# 26_Clocks_2.net
KiCad netlist of a schematic drawn in Altium Designer
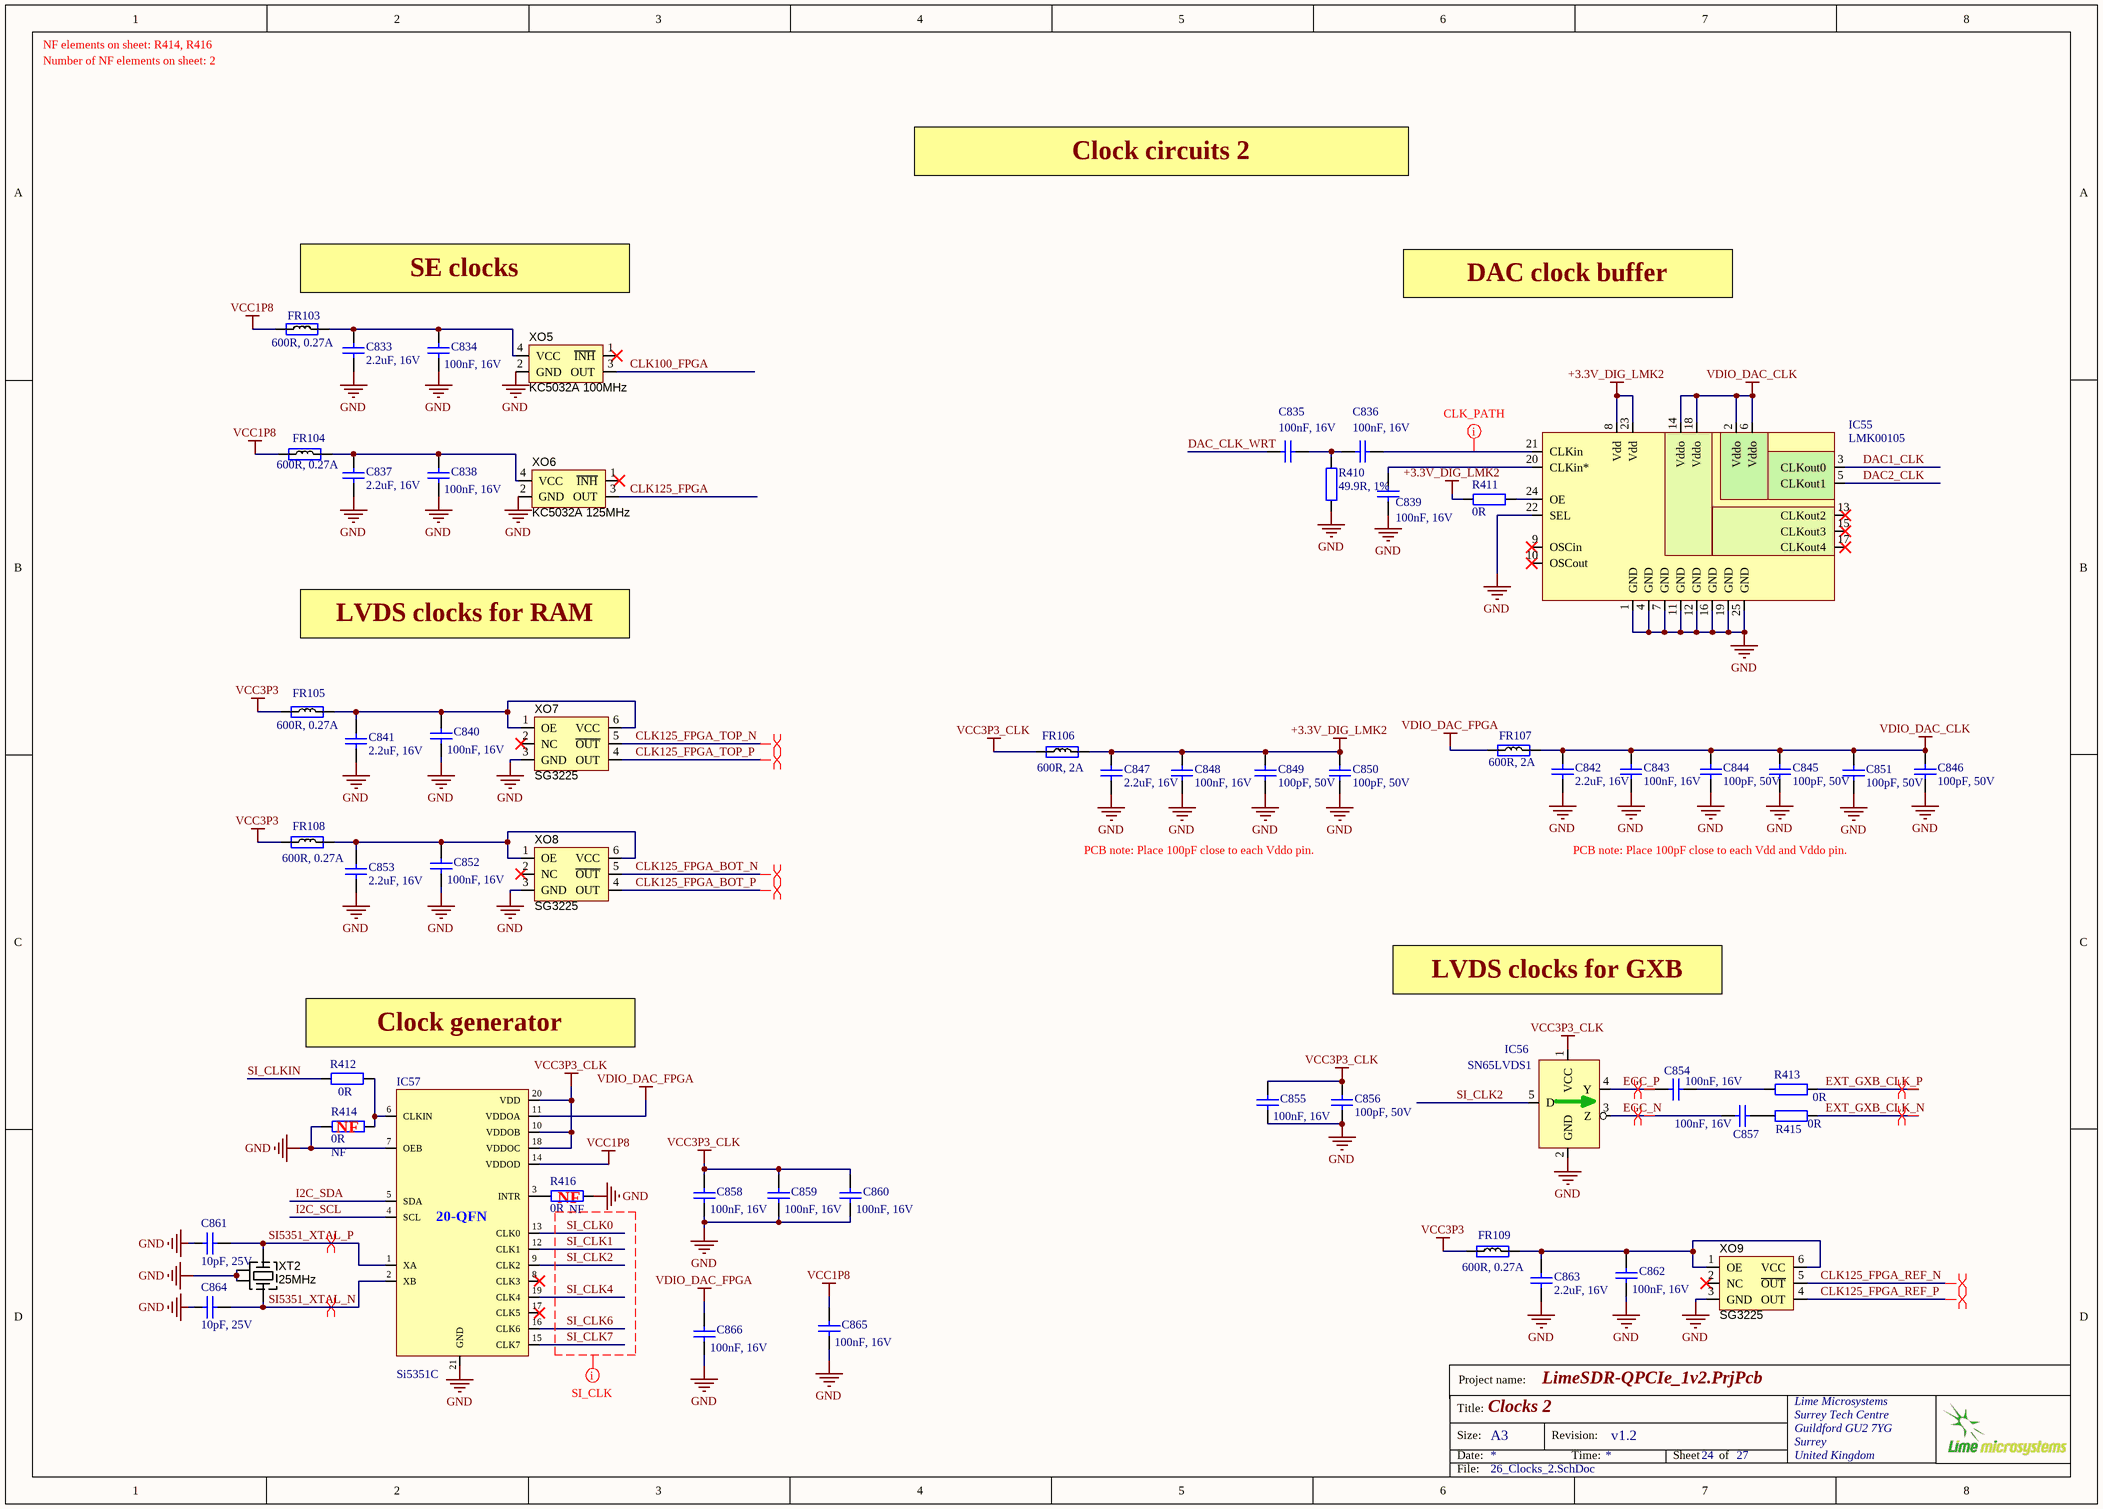
[diagram p0: 26_Clocks_2.SchDoc]

(export (version "E")
  (design (tool "Eeschema 10.0.6"))
  (components
    (comp (ref "C833")
      (value "2.2uF, 16V")
      (footprint "CAP0402")
      (description "CAP CER 2.2UF 16V 10% X5R 0402")
      (fields (field (name "MANUFACTURER") "TDK Corporation") (field (name "TOLERANCE") "±20%"))
      (libsource (lib "LimeMicroAltiumLib_schLib") (part "Cap_0402"))
    )
    (comp (ref "C834")
      (value "100nF, 16V")
      (footprint "CAP0402")
      (fields
        (field (name "TOLERANCE") "10 %")
        (field (name "MANUFACTURER") "Murata Electronics")
        (field (name "MANUFACTURER PART NUMBER") "GRM155R71C104KA88D")
      )
      (libsource (lib "LimeFPGAboard_schLib") (part "Cap_0603"))
    )
    (comp (ref "C835")
      (value "100nF, 16V")
      (footprint "CAP0402")
      (fields
        (field (name "MANUFACTURER") "Murata Electronics")
        (field (name "TOLERANCE") "10 %")
        (field (name "MANUFACTURER PART NUMBER") "GRM155R71C104KA88D")
      )
      (libsource (lib "LimeMicroAltiumLib_schLib") (part "Cap_0402"))
    )
    (comp (ref "C836")
      (value "100nF, 16V")
      (footprint "CAP0402")
      (fields
        (field (name "MANUFACTURER") "Murata Electronics")
        (field (name "TOLERANCE") "10 %")
        (field (name "MANUFACTURER PART NUMBER") "GRM155R71C104KA88D")
      )
      (libsource (lib "LimeMicroAltiumLib_schLib") (part "Cap_0402"))
    )
    (comp (ref "C837")
      (value "2.2uF, 16V")
      (footprint "CAP0402")
      (description "CAP CER 2.2UF 16V 10% X5R 0402")
      (fields (field (name "MANUFACTURER") "TDK Corporation") (field (name "TOLERANCE") "±20%"))
      (libsource (lib "LimeMicroAltiumLib_schLib") (part "Cap_0402"))
    )
    (comp (ref "C838")
      (value "100nF, 16V")
      (footprint "CAP0402")
      (fields
        (field (name "TOLERANCE") "10 %")
        (field (name "MANUFACTURER") "Murata Electronics")
        (field (name "MANUFACTURER PART NUMBER") "GRM155R71C104KA88D")
      )
      (libsource (lib "LimeFPGAboard_schLib") (part "Cap_0603"))
    )
    (comp (ref "C839")
      (value "100nF, 16V")
      (footprint "CAP0402")
      (fields
        (field (name "MANUFACTURER") "Murata Electronics")
        (field (name "TOLERANCE") "10 %")
        (field (name "MANUFACTURER PART NUMBER") "GRM155R71C104KA88D")
      )
      (libsource (lib "LimeMicroAltiumLib_schLib") (part "Cap_0402"))
    )
    (comp (ref "C840")
      (value "100nF, 16V")
      (footprint "CAP0402")
      (fields
        (field (name "TOLERANCE") "10 %")
        (field (name "MANUFACTURER") "Murata Electronics")
        (field (name "MANUFACTURER PART NUMBER") "GRM155R71C104KA88D")
      )
      (libsource (lib "LimeFPGAboard_schLib") (part "Cap_0603"))
    )
    (comp (ref "C841")
      (value "2.2uF, 16V")
      (footprint "CAP0402")
      (description "CAP CER 2.2UF 16V 10% X5R 0402")
      (fields (field (name "MANUFACTURER") "TDK Corporation") (field (name "TOLERANCE") "±20%"))
      (libsource (lib "LimeMicroAltiumLib_schLib") (part "Cap_0402"))
    )
    (comp (ref "C842")
      (value "2.2uF, 16V")
      (footprint "CAP0402")
      (description "CAP CER 2.2UF 16V 10% X5R 0402")
      (fields (field (name "MANUFACTURER") "TDK Corporation") (field (name "TOLERANCE") "±20%"))
      (libsource (lib "LimeMicroAltiumLib_schLib") (part "Cap_0402"))
    )
    (comp (ref "C843")
      (value "100nF, 16V")
      (footprint "CAP0402")
      (fields
        (field (name "MANUFACTURER") "Murata Electronics")
        (field (name "TOLERANCE") "10 %")
        (field (name "MANUFACTURER PART NUMBER") "GRM155R71C104KA88D")
      )
      (libsource (lib "LimeMicroAltiumLib_schLib") (part "Cap_0402"))
    )
    (comp (ref "C844")
      (value "100pF, 50V")
      (footprint "CAP0402")
      (fields (field (name "MANUFACTURER") "Yageo") (field (name "TOLERANCE") "±5%"))
      (libsource (lib "LimeMicroAltiumLib_schLib") (part "Cap_0402"))
    )
    (comp (ref "C845")
      (value "100pF, 50V")
      (footprint "CAP0402")
      (fields (field (name "MANUFACTURER") "Yageo") (field (name "TOLERANCE") "±5%"))
      (libsource (lib "LimeMicroAltiumLib_schLib") (part "Cap_0402"))
    )
    (comp (ref "C846")
      (value "100pF, 50V")
      (footprint "CAP0402")
      (fields (field (name "MANUFACTURER") "Yageo") (field (name "TOLERANCE") "±5%"))
      (libsource (lib "LimeMicroAltiumLib_schLib") (part "Cap_0402"))
    )
    (comp (ref "C847")
      (value "2.2uF, 16V")
      (footprint "CAP0402")
      (description "CAP CER 2.2UF 16V 10% X5R 0402")
      (fields (field (name "MANUFACTURER") "TDK Corporation") (field (name "TOLERANCE") "±20%"))
      (libsource (lib "LimeMicroAltiumLib_schLib") (part "Cap_0402"))
    )
    (comp (ref "C848")
      (value "100nF, 16V")
      (footprint "CAP0402")
      (fields
        (field (name "MANUFACTURER") "Murata Electronics")
        (field (name "TOLERANCE") "10 %")
        (field (name "MANUFACTURER PART NUMBER") "GRM155R71C104KA88D")
      )
      (libsource (lib "LimeMicroAltiumLib_schLib") (part "Cap_0402"))
    )
    (comp (ref "C849")
      (value "100pF, 50V")
      (footprint "CAP0402")
      (fields (field (name "MANUFACTURER") "Yageo") (field (name "TOLERANCE") "±5%"))
      (libsource (lib "LimeMicroAltiumLib_schLib") (part "Cap_0402"))
    )
    (comp (ref "C850")
      (value "100pF, 50V")
      (footprint "CAP0402")
      (fields (field (name "MANUFACTURER") "Yageo") (field (name "TOLERANCE") "±5%"))
      (libsource (lib "LimeMicroAltiumLib_schLib") (part "Cap_0402"))
    )
    (comp (ref "C851")
      (value "100pF, 50V")
      (footprint "CAP0402")
      (fields (field (name "MANUFACTURER") "Yageo") (field (name "TOLERANCE") "±5%"))
      (libsource (lib "LimeMicroAltiumLib_schLib") (part "Cap_0402"))
    )
    (comp (ref "C852")
      (value "100nF, 16V")
      (footprint "CAP0402")
      (fields
        (field (name "TOLERANCE") "10 %")
        (field (name "MANUFACTURER") "Murata Electronics")
        (field (name "MANUFACTURER PART NUMBER") "GRM155R71C104KA88D")
      )
      (libsource (lib "LimeFPGAboard_schLib") (part "Cap_0603"))
    )
    (comp (ref "C853")
      (value "2.2uF, 16V")
      (footprint "CAP0402")
      (description "CAP CER 2.2UF 16V 10% X5R 0402")
      (fields (field (name "MANUFACTURER") "TDK Corporation") (field (name "TOLERANCE") "±20%"))
      (libsource (lib "LimeMicroAltiumLib_schLib") (part "Cap_0402"))
    )
    (comp (ref "C854")
      (value "100nF, 16V")
      (footprint "CAP0402")
      (fields
        (field (name "TOLERANCE") "10 %")
        (field (name "MANUFACTURER") "Murata Electronics")
        (field (name "MANUFACTURER PART NUMBER") "GRM155R71C104KA88D")
      )
      (libsource (lib "LimeFPGAboard_schLib") (part "Cap_0603"))
    )
    (comp (ref "C855")
      (value "100nF, 16V")
      (footprint "CAP0402")
      (fields
        (field (name "TOLERANCE") "10 %")
        (field (name "MANUFACTURER") "Murata Electronics")
        (field (name "MANUFACTURER PART NUMBER") "GRM155R71C104KA88D")
      )
      (libsource (lib "LimeFPGAboard_schLib") (part "Cap_0603"))
    )
    (comp (ref "C856")
      (value "100pF, 50V")
      (footprint "CAP0402")
      (fields (field (name "MANUFACTURER") "Yageo") (field (name "TOLERANCE") "±5%"))
      (libsource (lib "LimeMicroAltiumLib_schLib") (part "Cap_0402"))
    )
    (comp (ref "C857")
      (value "100nF, 16V")
      (footprint "CAP0402")
      (fields
        (field (name "TOLERANCE") "10 %")
        (field (name "MANUFACTURER") "Murata Electronics")
        (field (name "MANUFACTURER PART NUMBER") "GRM155R71C104KA88D")
      )
      (libsource (lib "LimeFPGAboard_schLib") (part "Cap_0603"))
    )
    (comp (ref "C858")
      (value "100nF, 16V")
      (footprint "CAP0402")
      (fields
        (field (name "TOLERANCE") "10 %")
        (field (name "MANUFACTURER") "Murata Electronics")
        (field (name "MANUFACTURER PART NUMBER") "GRM155R71C104KA88D")
      )
      (libsource (lib "LimeFPGAboard_schLib") (part "Cap_0603"))
    )
    (comp (ref "C859")
      (value "100nF, 16V")
      (footprint "CAP0402")
      (fields
        (field (name "TOLERANCE") "10 %")
        (field (name "MANUFACTURER") "Murata Electronics")
        (field (name "MANUFACTURER PART NUMBER") "GRM155R71C104KA88D")
      )
      (libsource (lib "LimeFPGAboard_schLib") (part "Cap_0603"))
    )
    (comp (ref "C860")
      (value "100nF, 16V")
      (footprint "CAP0402")
      (fields
        (field (name "TOLERANCE") "10 %")
        (field (name "MANUFACTURER") "Murata Electronics")
        (field (name "MANUFACTURER PART NUMBER") "GRM155R71C104KA88D")
      )
      (libsource (lib "LimeFPGAboard_schLib") (part "Cap_0603"))
    )
    (comp (ref "C861")
      (value "10pF, 25V")
      (footprint "CAP0402")
      (fields (field (name "MANUFACTURER") "AVX"))
      (libsource (lib "LimeFPGAboard_schLib") (part "Cap_0402"))
    )
    (comp (ref "C862")
      (value "100nF, 16V")
      (footprint "CAP0402")
      (fields
        (field (name "TOLERANCE") "10 %")
        (field (name "MANUFACTURER") "Murata Electronics")
        (field (name "MANUFACTURER PART NUMBER") "GRM155R71C104KA88D")
      )
      (libsource (lib "LimeFPGAboard_schLib") (part "Cap_0603"))
    )
    (comp (ref "C863")
      (value "2.2uF, 16V")
      (footprint "CAP0402")
      (description "CAP CER 2.2UF 16V 10% X5R 0402")
      (fields (field (name "MANUFACTURER") "TDK Corporation") (field (name "TOLERANCE") "±20%"))
      (libsource (lib "LimeMicroAltiumLib_schLib") (part "Cap_0402"))
    )
    (comp (ref "C864")
      (value "10pF, 25V")
      (footprint "CAP0402")
      (fields (field (name "MANUFACTURER") "AVX"))
      (libsource (lib "LimeFPGAboard_schLib") (part "Cap_0402"))
    )
    (comp (ref "C865")
      (value "100nF, 16V")
      (footprint "CAP0402")
      (fields
        (field (name "TOLERANCE") "10 %")
        (field (name "MANUFACTURER") "Murata Electronics")
        (field (name "MANUFACTURER PART NUMBER") "GRM155R71C104KA88D")
      )
      (libsource (lib "LimeFPGAboard_schLib") (part "Cap_0603"))
    )
    (comp (ref "C866")
      (value "100nF, 16V")
      (footprint "CAP0402")
      (fields
        (field (name "TOLERANCE") "10 %")
        (field (name "MANUFACTURER") "Murata Electronics")
        (field (name "MANUFACTURER PART NUMBER") "GRM155R71C104KA88D")
      )
      (libsource (lib "LimeFPGAboard_schLib") (part "Cap_0603"))
    )
    (comp (ref "FR103")
      (value "600R, 0.27A")
      (footprint "RES0201")
      (fields (field (name "MANUFACTURER") "Taiyo Yuden") (field (name "Comment") "Ferrite"))
      (libsource (lib "LimeMicroAltiumLib_schLib") (part "Ferrite"))
    )
    (comp (ref "FR104")
      (value "600R, 0.27A")
      (footprint "RES0201")
      (fields (field (name "MANUFACTURER") "Taiyo Yuden") (field (name "Comment") "Ferrite"))
      (libsource (lib "LimeMicroAltiumLib_schLib") (part "Ferrite"))
    )
    (comp (ref "FR105")
      (value "600R, 0.27A")
      (footprint "RES0201")
      (fields (field (name "MANUFACTURER") "Taiyo Yuden") (field (name "Comment") "Ferrite"))
      (libsource (lib "LimeMicroAltiumLib_schLib") (part "Ferrite"))
    )
    (comp (ref "FR106")
      (value "600R, 2A")
      (footprint "RES0805")
      (fields (field (name "MANUFACTURER") "TDK"))
      (libsource (lib "LimeMicroAltiumLib_schLib") (part "Ferrite"))
    )
    (comp (ref "FR107")
      (value "600R, 2A")
      (footprint "RES0805")
      (fields (field (name "MANUFACTURER") "TDK"))
      (libsource (lib "LimeMicroAltiumLib_schLib") (part "Ferrite"))
    )
    (comp (ref "FR108")
      (value "600R, 0.27A")
      (footprint "RES0201")
      (fields (field (name "MANUFACTURER") "Taiyo Yuden") (field (name "Comment") "Ferrite"))
      (libsource (lib "LimeMicroAltiumLib_schLib") (part "Ferrite"))
    )
    (comp (ref "FR109")
      (value "600R, 0.27A")
      (footprint "RES0201")
      (fields (field (name "MANUFACTURER") "Taiyo Yuden") (field (name "Comment") "Ferrite"))
      (libsource (lib "LimeMicroAltiumLib_schLib") (part "Ferrite"))
    )
    (comp (ref "IC55")
      (value "LMK00105")
      (footprint "LMK00105SQ")
      (fields (field (name "MANUFACTURER") "Texas Instruments"))
      (libsource (lib "LimeMicroAltiumLib_schLib") (part "LMK00105"))
    )
    (comp (ref "IC56")
      (value "SN65LVDS1")
      (footprint "SOT23-5")
      (fields (field (name "MANUFACTURER") "TEXAS INSTRUMENTS"))
      (libsource (lib "LimeMicroAltiumLib_schLib") (part "SN65LVDS1"))
    )
    (comp (ref "IC57")
      (value "Si5351C")
      (footprint "Si5351C_20QFN")
      (fields (field (name "MANUFACTURER") "Silicon Labs"))
      (libsource (lib "LimeFPGAboard_schLib") (part "Si5351C"))
    )
    (comp (ref "R410")
      (value "49.9R, 1%")
      (footprint "RES0402")
      (fields
        (field (name "TOLERANCE") "±1%")
        (field (name "MANUFACTURER") "Samsung Electro-Mechanics America, Inc.")
      )
      (libsource (lib "LimeMicroAltiumLib_schLib") (part "Res_0402"))
    )
    (comp (ref "R411")
      (value "0R")
      (footprint "RES0402")
      (fields (field (name "MANUFACTURER") "Yageo") (field (name "TOLERANCE") "Jumper"))
      (libsource (lib "LimeMicroAltiumLib_schLib") (part "Res_0402"))
    )
    (comp (ref "R412")
      (value "0R")
      (footprint "RES0402")
      (fields (field (name "MANUFACTURER") "Yageo") (field (name "TOLERANCE") "Jumper"))
      (libsource (lib "LimeMicroAltiumLib_schLib") (part "Res_0402"))
    )
    (comp (ref "R413")
      (value "0R")
      (footprint "RES0402")
      (fields (field (name "MANUFACTURER") "Yageo") (field (name "TOLERANCE") "Jumper"))
      (libsource (lib "LimeMicroAltiumLib_schLib") (part "Res_0402"))
    )
    (comp (ref "R414")
      (value "0R")
      (footprint "RES0402")
      (fields
        (field (name "ASSEMBLY INFO") "NF")
        (field (name "MANUFACTURER") "Yageo")
        (field (name "TOLERANCE") "Jumper")
      )
      (libsource (lib "LimeMicroAltiumLib_schLib") (part "Res_0402"))
    )
    (comp (ref "R415")
      (value "0R")
      (footprint "RES0402")
      (fields (field (name "MANUFACTURER") "Yageo") (field (name "TOLERANCE") "Jumper"))
      (libsource (lib "LimeMicroAltiumLib_schLib") (part "Res_0402"))
    )
    (comp (ref "R416")
      (value "0R")
      (footprint "RES0402")
      (fields
        (field (name "ASSEMBLY INFO") "NF")
        (field (name "MANUFACTURER") "Yageo")
        (field (name "TOLERANCE") "Jumper")
      )
      (libsource (lib "LimeMicroAltiumLib_schLib") (part "Res_0402"))
    )
    (comp (ref "XO5")
      (value "KC5032A 100MHz")
      (footprint "CRYSTAL_4-LCC_v4")
      (description "Oscillator Crystal")
      (fields (field (name "MANUFACTURER") "AVX Corp/Kyocera Corp"))
      (libsource (lib "LimeMicroAltiumLib_schLib") (part "CRYSTAL"))
    )
    (comp (ref "XO6")
      (value "KC5032A 125MHz")
      (footprint "CRYSTAL_4-LCC_v4")
      (description "Oscillator Crystal")
      (fields (field (name "MANUFACTURER") "AVX Corp/Kyocera Corp"))
      (libsource (lib "LimeMicroAltiumLib_schLib") (part "CRYSTAL"))
    )
    (comp (ref "XO7")
      (value "SG3225")
      (footprint "CRYSTAL_6-LCC")
      (description "Oscillator Crystal")
      (fields (field (name "MANUFACTURER") "EPSON"))
      (libsource (lib "LimeMicroAltiumLib_schLib") (part "CRYSTAL_SG3225"))
    )
    (comp (ref "XO8")
      (value "SG3225")
      (footprint "CRYSTAL_6-LCC")
      (description "Oscillator Crystal")
      (fields (field (name "MANUFACTURER") "EPSON"))
      (libsource (lib "LimeMicroAltiumLib_schLib") (part "CRYSTAL_SG3225"))
    )
    (comp (ref "XO9")
      (value "SG3225")
      (footprint "CRYSTAL_6-LCC")
      (description "Oscillator Crystal")
      (fields (field (name "MANUFACTURER") "EPSON"))
      (libsource (lib "LimeMicroAltiumLib_schLib") (part "CRYSTAL_SG3225"))
    )
    (comp (ref "XT2")
      (value "25MHz")
      (footprint "CRYSTAL_4-LCC")
      (description "Oscillator Crystal 25 MHz")
      (fields (field (name "MANUFACTURER") "ABRACON"))
      (libsource (lib "LimeFPGAboard_schLib") (part "CRYSTAL_19M2"))
    )
  )
  (nets
    (net (code "1") (name "+3.3V_DIG_LMK2") (class "Default")
      (node (ref "C847") (pin "2") (pinfunction "2_2") (pintype "passive"))
      (node (ref "C848") (pin "2") (pinfunction "2_2") (pintype "passive"))
      (node (ref "C849") (pin "2") (pinfunction "2_2") (pintype "passive"))
      (node (ref "C850") (pin "2") (pinfunction "2_2") (pintype "passive"))
      (node (ref "FR106") (pin "2") (pinfunction "2_2") (pintype "passive"))
      (node (ref "IC55") (pin "23") (pinfunction "Vdd_23") (pintype "passive"))
      (node (ref "IC55") (pin "8") (pinfunction "Vdd_8") (pintype "passive"))
      (node (ref "R411") (pin "1") (pinfunction "1_1") (pintype "passive"))
    )
    (net (code "2") (name "/CLK100_FPGA") (class "Default")
      (node (ref "XO5") (pin "3") (pinfunction "OUT_3") (pintype "passive"))
    )
    (net (code "3") (name "/CLK125_FPGA") (class "Default")
      (node (ref "XO6") (pin "3") (pinfunction "OUT_3") (pintype "passive"))
    )
    (net (code "4") (name "/CLK125_FPGA_BOT_N") (class "Default")
      (node (ref "XO8") (pin "5") (pinfunction "~{OUT}_5") (pintype "passive"))
    )
    (net (code "5") (name "/CLK125_FPGA_BOT_P") (class "Default")
      (node (ref "XO8") (pin "4") (pinfunction "OUT_4") (pintype "passive"))
    )
    (net (code "6") (name "/CLK125_FPGA_REF_N") (class "Default")
      (node (ref "XO9") (pin "5") (pinfunction "~{OUT}_5") (pintype "passive"))
    )
    (net (code "7") (name "/CLK125_FPGA_REF_P") (class "Default")
      (node (ref "XO9") (pin "4") (pinfunction "OUT_4") (pintype "passive"))
    )
    (net (code "8") (name "/CLK125_FPGA_TOP_N") (class "Default")
      (node (ref "XO7") (pin "5") (pinfunction "~{OUT}_5") (pintype "passive"))
    )
    (net (code "9") (name "/CLK125_FPGA_TOP_P") (class "Default")
      (node (ref "XO7") (pin "4") (pinfunction "OUT_4") (pintype "passive"))
    )
    (net (code "10") (name "/DAC1_CLK") (class "Default")
      (node (ref "IC55") (pin "3") (pinfunction "CLKout0_3") (pintype "passive"))
    )
    (net (code "11") (name "/DAC2_CLK") (class "Default")
      (node (ref "IC55") (pin "5") (pinfunction "CLKout1_5") (pintype "passive"))
    )
    (net (code "12") (name "/DAC_CLK_WRT") (class "Default")
      (node (ref "C835") (pin "2") (pinfunction "2_2") (pintype "passive"))
    )
    (net (code "13") (name "/EGC_N") (class "Default")
      (node (ref "C857") (pin "1") (pinfunction "1_1") (pintype "passive"))
      (node (ref "IC56") (pin "3") (pinfunction "Z_3") (pintype "passive"))
    )
    (net (code "14") (name "/EGC_P") (class "Default")
      (node (ref "C854") (pin "1") (pinfunction "1_1") (pintype "passive"))
      (node (ref "IC56") (pin "4") (pinfunction "Y_4") (pintype "passive"))
    )
    (net (code "15") (name "/EXT_GXB_CLK_N") (class "Default")
      (node (ref "R415") (pin "1") (pinfunction "1_1") (pintype "passive"))
    )
    (net (code "16") (name "/EXT_GXB_CLK_P") (class "Default")
      (node (ref "R413") (pin "1") (pinfunction "1_1") (pintype "passive"))
    )
    (net (code "17") (name "/I2C_SCL") (class "Default")
      (node (ref "IC57") (pin "4") (pinfunction "SCL_4") (pintype "passive"))
    )
    (net (code "18") (name "/I2C_SDA") (class "Default")
      (node (ref "IC57") (pin "5") (pinfunction "SDA_5") (pintype "passive"))
    )
    (net (code "19") (name "/SI5351_XTAL_N") (class "Default")
      (node (ref "C864") (pin "2") (pinfunction "2_2") (pintype "passive"))
      (node (ref "IC57") (pin "2") (pinfunction "XB_2") (pintype "passive"))
      (node (ref "XT2") (pin "3") (pinfunction "X_3") (pintype "passive"))
    )
    (net (code "20") (name "/SI5351_XTAL_P") (class "Default")
      (node (ref "C861") (pin "2") (pinfunction "2_2") (pintype "passive"))
      (node (ref "IC57") (pin "1") (pinfunction "XA_1") (pintype "passive"))
      (node (ref "XT2") (pin "1") (pinfunction "X_1") (pintype "passive"))
    )
    (net (code "21") (name "/SI_CLK0") (class "Default")
      (node (ref "IC57") (pin "13") (pinfunction "CLK0_13") (pintype "passive"))
    )
    (net (code "22") (name "/SI_CLK1") (class "Default")
      (node (ref "IC57") (pin "12") (pinfunction "CLK1_12") (pintype "passive"))
    )
    (net (code "23") (name "/SI_CLK2") (class "Default")
      (node (ref "IC56") (pin "5") (pinfunction "D_5") (pintype "passive"))
      (node (ref "IC57") (pin "9") (pinfunction "CLK2_9") (pintype "passive"))
    )
    (net (code "24") (name "/SI_CLK4") (class "Default")
      (node (ref "IC57") (pin "19") (pinfunction "CLK4_19") (pintype "passive"))
    )
    (net (code "25") (name "/SI_CLK6") (class "Default")
      (node (ref "IC57") (pin "16") (pinfunction "CLK6_16") (pintype "passive"))
    )
    (net (code "26") (name "/SI_CLK7") (class "Default")
      (node (ref "IC57") (pin "15") (pinfunction "CLK7_15") (pintype "passive"))
    )
    (net (code "27") (name "/SI_CLKIN") (class "Default")
      (node (ref "R412") (pin "1") (pinfunction "1_1") (pintype "passive"))
    )
    (net (code "28") (name "GND") (class "Default")
      (node (ref "C833") (pin "1") (pinfunction "1_1") (pintype "passive"))
      (node (ref "C834") (pin "2") (pinfunction "2_2") (pintype "passive"))
      (node (ref "C837") (pin "1") (pinfunction "1_1") (pintype "passive"))
      (node (ref "C838") (pin "2") (pinfunction "2_2") (pintype "passive"))
      (node (ref "C839") (pin "1") (pinfunction "1_1") (pintype "passive"))
      (node (ref "C840") (pin "2") (pinfunction "2_2") (pintype "passive"))
      (node (ref "C841") (pin "1") (pinfunction "1_1") (pintype "passive"))
      (node (ref "C842") (pin "1") (pinfunction "1_1") (pintype "passive"))
      (node (ref "C843") (pin "1") (pinfunction "1_1") (pintype "passive"))
      (node (ref "C844") (pin "1") (pinfunction "1_1") (pintype "passive"))
      (node (ref "C845") (pin "1") (pinfunction "1_1") (pintype "passive"))
      (node (ref "C846") (pin "1") (pinfunction "1_1") (pintype "passive"))
      (node (ref "C847") (pin "1") (pinfunction "1_1") (pintype "passive"))
      (node (ref "C848") (pin "1") (pinfunction "1_1") (pintype "passive"))
      (node (ref "C849") (pin "1") (pinfunction "1_1") (pintype "passive"))
      (node (ref "C850") (pin "1") (pinfunction "1_1") (pintype "passive"))
      (node (ref "C851") (pin "1") (pinfunction "1_1") (pintype "passive"))
      (node (ref "C852") (pin "2") (pinfunction "2_2") (pintype "passive"))
      (node (ref "C853") (pin "1") (pinfunction "1_1") (pintype "passive"))
      (node (ref "C855") (pin "2") (pinfunction "2_2") (pintype "passive"))
      (node (ref "C856") (pin "1") (pinfunction "1_1") (pintype "passive"))
      (node (ref "C858") (pin "2") (pinfunction "2_2") (pintype "passive"))
      (node (ref "C859") (pin "2") (pinfunction "2_2") (pintype "passive"))
      (node (ref "C860") (pin "2") (pinfunction "2_2") (pintype "passive"))
      (node (ref "C861") (pin "1") (pinfunction "1_1") (pintype "passive"))
      (node (ref "C862") (pin "2") (pinfunction "2_2") (pintype "passive"))
      (node (ref "C863") (pin "1") (pinfunction "1_1") (pintype "passive"))
      (node (ref "C864") (pin "1") (pinfunction "1_1") (pintype "passive"))
      (node (ref "C865") (pin "2") (pinfunction "2_2") (pintype "passive"))
      (node (ref "C866") (pin "2") (pinfunction "2_2") (pintype "passive"))
      (node (ref "IC55") (pin "1") (pinfunction "GND_1") (pintype "passive"))
      (node (ref "IC55") (pin "11") (pinfunction "GND_11") (pintype "passive"))
      (node (ref "IC55") (pin "12") (pinfunction "GND_12") (pintype "passive"))
      (node (ref "IC55") (pin "16") (pinfunction "GND_16") (pintype "passive"))
      (node (ref "IC55") (pin "19") (pinfunction "GND_19") (pintype "passive"))
      (node (ref "IC55") (pin "22") (pinfunction "SEL_22") (pintype "passive"))
      (node (ref "IC55") (pin "25") (pinfunction "GND_25") (pintype "passive"))
      (node (ref "IC55") (pin "4") (pinfunction "GND_4") (pintype "passive"))
      (node (ref "IC55") (pin "7") (pinfunction "GND_7") (pintype "passive"))
      (node (ref "IC56") (pin "2") (pinfunction "GND_2") (pintype "passive"))
      (node (ref "IC57") (pin "21") (pinfunction "GND_21") (pintype "passive"))
      (node (ref "IC57") (pin "7") (pinfunction "OEB_7") (pintype "passive"))
      (node (ref "R410") (pin "1") (pinfunction "1_1") (pintype "passive"))
      (node (ref "R414") (pin "2") (pinfunction "2_2") (pintype "passive"))
      (node (ref "R416") (pin "1") (pinfunction "1_1") (pintype "passive"))
      (node (ref "XO5") (pin "2") (pinfunction "GND_2") (pintype "passive"))
      (node (ref "XO6") (pin "2") (pinfunction "GND_2") (pintype "passive"))
      (node (ref "XO7") (pin "3") (pinfunction "GND_3") (pintype "passive"))
      (node (ref "XO8") (pin "3") (pinfunction "GND_3") (pintype "passive"))
      (node (ref "XO9") (pin "3") (pinfunction "GND_3") (pintype "passive"))
      (node (ref "XT2") (pin "2") (pinfunction "GND_2") (pintype "passive"))
      (node (ref "XT2") (pin "4") (pinfunction "GND_4") (pintype "passive"))
    )
    (net (code "29") (name "Net-(C835-Pad1)") (class "Default")
      (node (ref "C835") (pin "1") (pinfunction "1_1") (pintype "passive"))
      (node (ref "C836") (pin "2") (pinfunction "2_2") (pintype "passive"))
      (node (ref "R410") (pin "2") (pinfunction "2_2") (pintype "passive"))
    )
    (net (code "30") (name "Net-(C854-Pad2)") (class "Default")
      (node (ref "C854") (pin "2") (pinfunction "2_2") (pintype "passive"))
      (node (ref "R413") (pin "2") (pinfunction "2_2") (pintype "passive"))
    )
    (net (code "31") (name "Net-(C857-Pad2)") (class "Default")
      (node (ref "C857") (pin "2") (pinfunction "2_2") (pintype "passive"))
      (node (ref "R415") (pin "2") (pinfunction "2_2") (pintype "passive"))
    )
    (net (code "32") (name "Net-(IC55-CLKin)") (class "Default")
      (node (ref "C836") (pin "1") (pinfunction "1_1") (pintype "passive"))
      (node (ref "IC55") (pin "21") (pinfunction "CLKin_21") (pintype "passive"))
    )
    (net (code "33") (name "Net-(IC55-CLKin*)") (class "Default")
      (node (ref "C839") (pin "2") (pinfunction "2_2") (pintype "passive"))
      (node (ref "IC55") (pin "20") (pinfunction "CLKin*_20") (pintype "passive"))
    )
    (net (code "34") (name "Net-(IC55-OE)") (class "Default")
      (node (ref "IC55") (pin "24") (pinfunction "OE_24") (pintype "passive"))
      (node (ref "R411") (pin "2") (pinfunction "2_2") (pintype "passive"))
    )
    (net (code "35") (name "Net-(IC57-CLKIN)") (class "Default")
      (node (ref "IC57") (pin "6") (pinfunction "CLKIN_6") (pintype "passive"))
      (node (ref "R412") (pin "2") (pinfunction "2_2") (pintype "passive"))
      (node (ref "R414") (pin "1") (pinfunction "1_1") (pintype "passive"))
    )
    (net (code "36") (name "Net-(IC57-INTR)") (class "Default")
      (node (ref "IC57") (pin "3") (pinfunction "INTR_3") (pintype "passive"))
      (node (ref "R416") (pin "2") (pinfunction "2_2") (pintype "passive"))
    )
    (net (code "37") (name "Net-(XO5-VCC)") (class "Default")
      (node (ref "C833") (pin "2") (pinfunction "2_2") (pintype "passive"))
      (node (ref "C834") (pin "1") (pinfunction "1_1") (pintype "passive"))
      (node (ref "FR103") (pin "2") (pinfunction "2_2") (pintype "passive"))
      (node (ref "XO5") (pin "4") (pinfunction "VCC_4") (pintype "passive"))
    )
    (net (code "38") (name "Net-(XO6-VCC)") (class "Default")
      (node (ref "C837") (pin "2") (pinfunction "2_2") (pintype "passive"))
      (node (ref "C838") (pin "1") (pinfunction "1_1") (pintype "passive"))
      (node (ref "FR104") (pin "2") (pinfunction "2_2") (pintype "passive"))
      (node (ref "XO6") (pin "4") (pinfunction "VCC_4") (pintype "passive"))
    )
    (net (code "39") (name "Net-(XO7-OE)") (class "Default")
      (node (ref "C840") (pin "1") (pinfunction "1_1") (pintype "passive"))
      (node (ref "C841") (pin "2") (pinfunction "2_2") (pintype "passive"))
      (node (ref "FR105") (pin "2") (pinfunction "2_2") (pintype "passive"))
      (node (ref "XO7") (pin "1") (pinfunction "OE_1") (pintype "passive"))
      (node (ref "XO7") (pin "6") (pinfunction "VCC_6") (pintype "power_in"))
    )
    (net (code "40") (name "Net-(XO8-OE)") (class "Default")
      (node (ref "C852") (pin "1") (pinfunction "1_1") (pintype "passive"))
      (node (ref "C853") (pin "2") (pinfunction "2_2") (pintype "passive"))
      (node (ref "FR108") (pin "2") (pinfunction "2_2") (pintype "passive"))
      (node (ref "XO8") (pin "1") (pinfunction "OE_1") (pintype "passive"))
      (node (ref "XO8") (pin "6") (pinfunction "VCC_6") (pintype "power_in"))
    )
    (net (code "41") (name "Net-(XO9-OE)") (class "Default")
      (node (ref "C862") (pin "1") (pinfunction "1_1") (pintype "passive"))
      (node (ref "C863") (pin "2") (pinfunction "2_2") (pintype "passive"))
      (node (ref "FR109") (pin "2") (pinfunction "2_2") (pintype "passive"))
      (node (ref "XO9") (pin "1") (pinfunction "OE_1") (pintype "passive"))
      (node (ref "XO9") (pin "6") (pinfunction "VCC_6") (pintype "power_in"))
    )
    (net (code "42") (name "VCC1P8") (class "Default")
      (node (ref "C865") (pin "1") (pinfunction "1_1") (pintype "passive"))
      (node (ref "FR103") (pin "1") (pinfunction "1_1") (pintype "passive"))
      (node (ref "FR104") (pin "1") (pinfunction "1_1") (pintype "passive"))
      (node (ref "IC57") (pin "14") (pinfunction "VDDOD_14") (pintype "passive"))
    )
    (net (code "43") (name "VCC3P3") (class "Default")
      (node (ref "FR105") (pin "1") (pinfunction "1_1") (pintype "passive"))
      (node (ref "FR108") (pin "1") (pinfunction "1_1") (pintype "passive"))
      (node (ref "FR109") (pin "1") (pinfunction "1_1") (pintype "passive"))
    )
    (net (code "44") (name "VCC3P3_CLK") (class "Default")
      (node (ref "C855") (pin "1") (pinfunction "1_1") (pintype "passive"))
      (node (ref "C856") (pin "2") (pinfunction "2_2") (pintype "passive"))
      (node (ref "C858") (pin "1") (pinfunction "1_1") (pintype "passive"))
      (node (ref "C859") (pin "1") (pinfunction "1_1") (pintype "passive"))
      (node (ref "C860") (pin "1") (pinfunction "1_1") (pintype "passive"))
      (node (ref "FR106") (pin "1") (pinfunction "1_1") (pintype "passive"))
      (node (ref "IC56") (pin "1") (pinfunction "VCC_1") (pintype "passive"))
      (node (ref "IC57") (pin "10") (pinfunction "VDDOB_10") (pintype "passive"))
      (node (ref "IC57") (pin "18") (pinfunction "VDDOC_18") (pintype "passive"))
      (node (ref "IC57") (pin "20") (pinfunction "VDD_20") (pintype "passive"))
    )
    (net (code "45") (name "VDIO_DAC_CLK") (class "Default")
      (node (ref "C842") (pin "2") (pinfunction "2_2") (pintype "passive"))
      (node (ref "C843") (pin "2") (pinfunction "2_2") (pintype "passive"))
      (node (ref "C844") (pin "2") (pinfunction "2_2") (pintype "passive"))
      (node (ref "C845") (pin "2") (pinfunction "2_2") (pintype "passive"))
      (node (ref "C846") (pin "2") (pinfunction "2_2") (pintype "passive"))
      (node (ref "C851") (pin "2") (pinfunction "2_2") (pintype "passive"))
      (node (ref "FR107") (pin "2") (pinfunction "2_2") (pintype "passive"))
      (node (ref "IC55") (pin "14") (pinfunction "Vddo_14") (pintype "passive"))
      (node (ref "IC55") (pin "18") (pinfunction "Vddo_18") (pintype "passive"))
      (node (ref "IC55") (pin "2") (pinfunction "Vddo_2") (pintype "passive"))
      (node (ref "IC55") (pin "6") (pinfunction "Vddo_6") (pintype "passive"))
    )
    (net (code "46") (name "VDIO_DAC_FPGA") (class "Default")
      (node (ref "C866") (pin "1") (pinfunction "1_1") (pintype "passive"))
      (node (ref "FR107") (pin "1") (pinfunction "1_1") (pintype "passive"))
      (node (ref "IC57") (pin "11") (pinfunction "VDDOA_11") (pintype "passive"))
    )
    (net (code "47") (name "unconnected-(IC55-CLKout2-Pad13)") (class "Default")
      (node (ref "IC55") (pin "13") (pinfunction "CLKout2_13") (pintype "passive+no_connect"))
    )
    (net (code "48") (name "unconnected-(IC55-CLKout3-Pad15)") (class "Default")
      (node (ref "IC55") (pin "15") (pinfunction "CLKout3_15") (pintype "passive+no_connect"))
    )
    (net (code "49") (name "unconnected-(IC55-CLKout4-Pad17)") (class "Default")
      (node (ref "IC55") (pin "17") (pinfunction "CLKout4_17") (pintype "passive+no_connect"))
    )
    (net (code "50") (name "unconnected-(IC55-OSCin-Pad9)") (class "Default")
      (node (ref "IC55") (pin "9") (pinfunction "OSCin_9") (pintype "passive+no_connect"))
    )
    (net (code "51") (name "unconnected-(IC55-OSCout-Pad10)") (class "Default")
      (node (ref "IC55") (pin "10") (pinfunction "OSCout_10") (pintype "passive+no_connect"))
    )
    (net (code "52") (name "unconnected-(IC57-CLK3-Pad8)") (class "Default")
      (node (ref "IC57") (pin "8") (pinfunction "CLK3_8") (pintype "passive+no_connect"))
    )
    (net (code "53") (name "unconnected-(IC57-CLK5-Pad17)") (class "Default")
      (node (ref "IC57") (pin "17") (pinfunction "CLK5_17") (pintype "passive+no_connect"))
    )
    (net (code "54") (name "unconnected-(XO5-~{INH}-Pad1)") (class "Default")
      (node (ref "XO5") (pin "1") (pinfunction "~{INH}_1") (pintype "passive+no_connect"))
    )
    (net (code "55") (name "unconnected-(XO6-~{INH}-Pad1)") (class "Default")
      (node (ref "XO6") (pin "1") (pinfunction "~{INH}_1") (pintype "passive+no_connect"))
    )
    (net (code "56") (name "unconnected-(XO7-NC-Pad2)") (class "Default")
      (node (ref "XO7") (pin "2") (pinfunction "NC_2") (pintype "passive+no_connect"))
    )
    (net (code "57") (name "unconnected-(XO8-NC-Pad2)") (class "Default")
      (node (ref "XO8") (pin "2") (pinfunction "NC_2") (pintype "passive+no_connect"))
    )
    (net (code "58") (name "unconnected-(XO9-NC-Pad2)") (class "Default")
      (node (ref "XO9") (pin "2") (pinfunction "NC_2") (pintype "passive+no_connect"))
    )
  )
)
